# stmotor.net
KiCad netlist of a schematic drawn in EAGLE
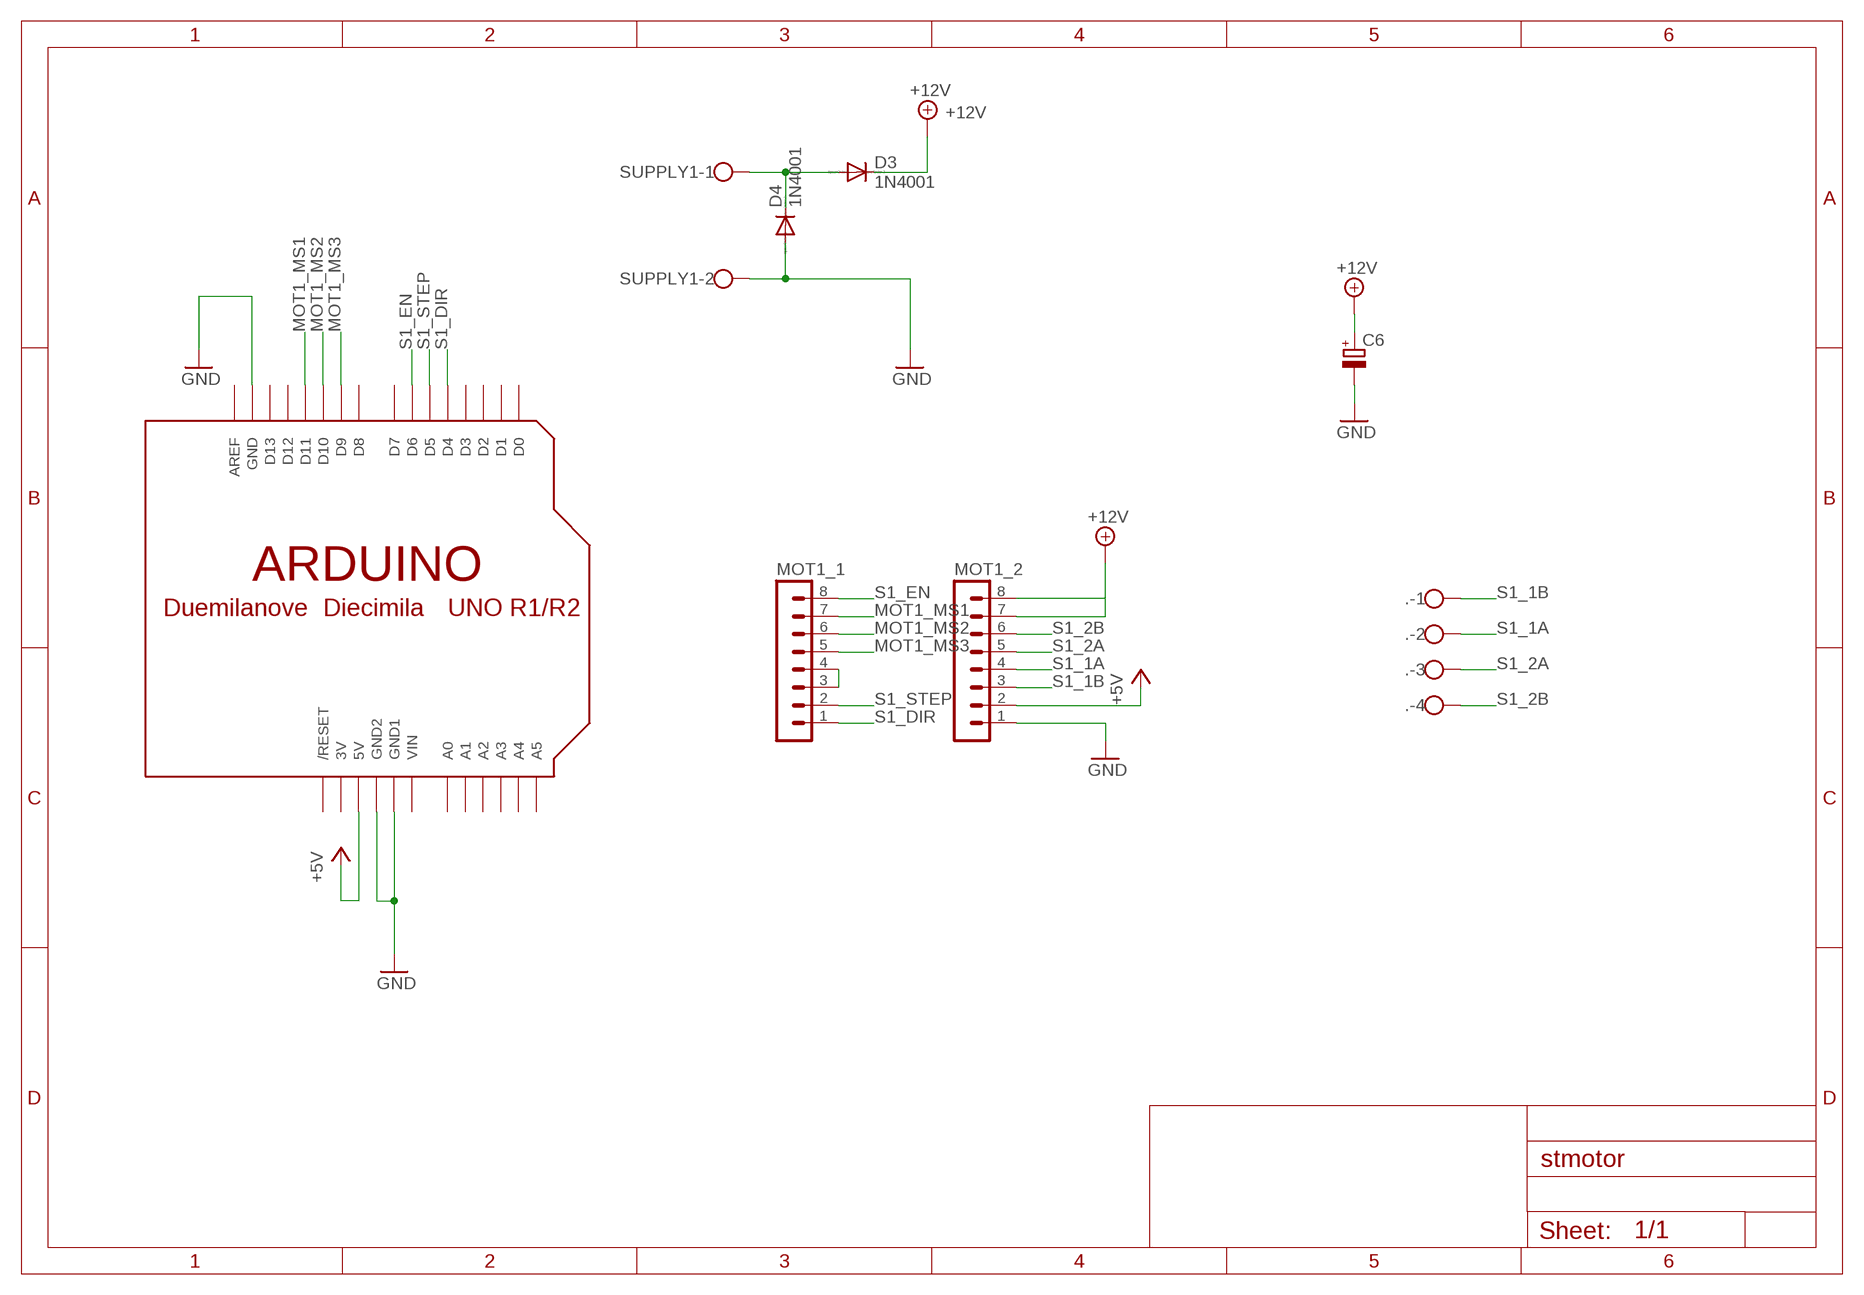
[diagram p0: schematic, sheet 1]

(export (version "E")
  (design (tool "Eeschema 10.0.6"))
  (components
    (comp (ref ".")
      (value "W237-4")
      (footprint "eagle-import:W237-4")
      (libsource (lib "eagle-import") (part "W237-4"))
    )
    (comp (ref "C6")
      (value "CPOL-EU153CLV-0807")
      (footprint "eagle-import:153CLV-0807")
      (libsource (lib "eagle-import") (part "CPOL-EU153CLV-0807"))
    )
    (comp (ref "D3")
      (value "1N4001")
      (footprint "eagle-import:DO41-10")
      (libsource (lib "eagle-import") (part "1N4004"))
    )
    (comp (ref "D4")
      (value "1N4001")
      (footprint "eagle-import:DO41-10")
      (libsource (lib "eagle-import") (part "1N4004"))
    )
    (comp (ref "MOT1_1")
      (value "MA08-1")
      (footprint "eagle-import:MA08-1")
      (libsource (lib "eagle-import") (part "MA08-1"))
    )
    (comp (ref "MOT1_2")
      (value "MA08-1")
      (footprint "eagle-import:MA08-1")
      (libsource (lib "eagle-import") (part "MA08-1"))
    )
    (comp (ref "SUPPLY1")
      (value "W237-102")
      (footprint "eagle-import:W237-102")
      (fields (field (name "MPN") "237-102"))
      (libsource (lib "eagle-import") (part "W237-102"))
    )
    (comp (ref "U$1")
      (value "ARDUINO-NOHOLE")
      (footprint "eagle-import:ARDUINO-NOHOLE")
      (libsource (lib "eagle-import") (part "ARDUINO-NOHOLE"))
    )
  )
  (nets
    (net (code "1") (name "+5V") (class "Default")
      (node (ref "MOT1_2") (pin "2") (pinfunction "2_2") (pintype "passive"))
      (node (ref "U$1") (pin "5V") (pinfunction "5V_5V") (pintype "power_in"))
    )
    (net (code "2") (name "+12V") (class "Default")
      (node (ref "C6") (pin "+") (pinfunction "+_+") (pintype "passive"))
      (node (ref "D3") (pin "C") (pinfunction "C_C") (pintype "passive"))
      (node (ref "MOT1_2") (pin "7") (pinfunction "7_7") (pintype "passive"))
    )
    (net (code "3") (name "/3V") (class "Default")
      (node (ref "U$1") (pin "3V") (pinfunction "3V_3V") (pintype "power_in"))
    )
    (net (code "4") (name "/MOT1_MS1") (class "Default")
      (node (ref "MOT1_1") (pin "7") (pinfunction "7_7") (pintype "passive"))
      (node (ref "U$1") (pin "D11") (pinfunction "D11_D11") (pintype "bidirectional"))
    )
    (net (code "5") (name "/MOT1_MS2") (class "Default")
      (node (ref "MOT1_1") (pin "6") (pinfunction "6_6") (pintype "passive"))
      (node (ref "U$1") (pin "D10") (pinfunction "D10_D10") (pintype "bidirectional"))
    )
    (net (code "6") (name "/MOT1_MS3") (class "Default")
      (node (ref "MOT1_1") (pin "5") (pinfunction "5_5") (pintype "passive"))
      (node (ref "U$1") (pin "D9") (pinfunction "D9_D9") (pintype "bidirectional"))
    )
    (net (code "7") (name "/S1_1A") (class "Default")
      (node (ref ".") (pin "2") (pinfunction "KL_2") (pintype "passive"))
      (node (ref "MOT1_2") (pin "4") (pinfunction "4_4") (pintype "passive"))
    )
    (net (code "8") (name "/S1_1B") (class "Default")
      (node (ref ".") (pin "1") (pinfunction "KL_1") (pintype "passive"))
      (node (ref "MOT1_2") (pin "3") (pinfunction "3_3") (pintype "passive"))
    )
    (net (code "9") (name "/S1_2A") (class "Default")
      (node (ref ".") (pin "3") (pinfunction "KL_3") (pintype "passive"))
      (node (ref "MOT1_2") (pin "5") (pinfunction "5_5") (pintype "passive"))
    )
    (net (code "10") (name "/S1_2B") (class "Default")
      (node (ref ".") (pin "4") (pinfunction "KL_4") (pintype "passive"))
      (node (ref "MOT1_2") (pin "6") (pinfunction "6_6") (pintype "passive"))
    )
    (net (code "11") (name "/S1_DIR") (class "Default")
      (node (ref "MOT1_1") (pin "1") (pinfunction "1_1") (pintype "passive"))
      (node (ref "U$1") (pin "D4") (pinfunction "D4_D4") (pintype "bidirectional"))
    )
    (net (code "12") (name "/S1_EN") (class "Default")
      (node (ref "MOT1_1") (pin "8") (pinfunction "8_8") (pintype "passive"))
      (node (ref "U$1") (pin "D6") (pinfunction "D6_D6") (pintype "bidirectional"))
    )
    (net (code "13") (name "/S1_STEP") (class "Default")
      (node (ref "MOT1_1") (pin "2") (pinfunction "2_2") (pintype "passive"))
      (node (ref "U$1") (pin "D5") (pinfunction "D5_D5") (pintype "bidirectional"))
    )
    (net (code "14") (name "/VIN") (class "Default")
      (node (ref "U$1") (pin "VIN") (pinfunction "VIN_VIN") (pintype "power_in"))
    )
    (net (code "15") (name "GND") (class "Default")
      (node (ref "C6") (pin "-") (pinfunction "-_-") (pintype "passive"))
      (node (ref "D4") (pin "A") (pinfunction "A_A") (pintype "passive"))
      (node (ref "MOT1_2") (pin "1") (pinfunction "1_1") (pintype "passive"))
      (node (ref "SUPPLY1") (pin "2") (pinfunction "KL_2") (pintype "passive"))
      (node (ref "U$1") (pin "GND") (pinfunction "GND_GND") (pintype "power_in"))
      (node (ref "U$1") (pin "GND1") (pinfunction "GND1_GND1") (pintype "power_in"))
      (node (ref "U$1") (pin "GND2") (pinfunction "GND2_GND2") (pintype "power_in"))
    )
    (net (code "16") (name "Net-(MOT1_1-Pad3)") (class "Default")
      (node (ref "MOT1_1") (pin "3") (pinfunction "3_3") (pintype "passive"))
      (node (ref "MOT1_1") (pin "4") (pinfunction "4_4") (pintype "passive"))
    )
    (net (code "17") (name "Net-(SUPPLY1A-KL)") (class "Default")
      (node (ref "D3") (pin "A") (pinfunction "A_A") (pintype "passive"))
      (node (ref "D4") (pin "C") (pinfunction "C_C") (pintype "passive"))
      (node (ref "SUPPLY1") (pin "1") (pinfunction "KL_1") (pintype "passive"))
    )
    (net (code "18") (name "unconnected-(MOT1_2-Pad8)") (class "Default")
      (node (ref "MOT1_2") (pin "8") (pinfunction "8_8") (pintype "passive"))
    )
    (net (code "19") (name "unconnected-(U$1-PadA0)") (class "Default")
      (node (ref "U$1") (pin "A0") (pinfunction "A0_A0") (pintype "bidirectional"))
    )
    (net (code "20") (name "unconnected-(U$1-PadA1)") (class "Default")
      (node (ref "U$1") (pin "A1") (pinfunction "A1_A1") (pintype "bidirectional"))
    )
    (net (code "21") (name "unconnected-(U$1-PadA2)") (class "Default")
      (node (ref "U$1") (pin "A2") (pinfunction "A2_A2") (pintype "bidirectional"))
    )
    (net (code "22") (name "unconnected-(U$1-PadA3)") (class "Default")
      (node (ref "U$1") (pin "A3") (pinfunction "A3_A3") (pintype "bidirectional"))
    )
    (net (code "23") (name "unconnected-(U$1-PadA4)") (class "Default")
      (node (ref "U$1") (pin "A4") (pinfunction "A4_A4") (pintype "bidirectional"))
    )
    (net (code "24") (name "unconnected-(U$1-PadA5)") (class "Default")
      (node (ref "U$1") (pin "A5") (pinfunction "A5_A5") (pintype "bidirectional"))
    )
    (net (code "25") (name "unconnected-(U$1-PadAREF)") (class "Default")
      (node (ref "U$1") (pin "AREF") (pinfunction "AREF_AREF") (pintype "bidirectional"))
    )
    (net (code "26") (name "unconnected-(U$1-PadD0)") (class "Default")
      (node (ref "U$1") (pin "D0") (pinfunction "D0_D0") (pintype "bidirectional"))
    )
    (net (code "27") (name "unconnected-(U$1-PadD1)") (class "Default")
      (node (ref "U$1") (pin "D1") (pinfunction "D1_D1") (pintype "bidirectional"))
    )
    (net (code "28") (name "unconnected-(U$1-PadD2)") (class "Default")
      (node (ref "U$1") (pin "D2") (pinfunction "D2_D2") (pintype "bidirectional"))
    )
    (net (code "29") (name "unconnected-(U$1-PadD3)") (class "Default")
      (node (ref "U$1") (pin "D3") (pinfunction "D3_D3") (pintype "bidirectional"))
    )
    (net (code "30") (name "unconnected-(U$1-PadD7)") (class "Default")
      (node (ref "U$1") (pin "D7") (pinfunction "D7_D7") (pintype "bidirectional"))
    )
    (net (code "31") (name "unconnected-(U$1-PadD8)") (class "Default")
      (node (ref "U$1") (pin "D8") (pinfunction "D8_D8") (pintype "bidirectional"))
    )
    (net (code "32") (name "unconnected-(U$1-PadD12)") (class "Default")
      (node (ref "U$1") (pin "D12") (pinfunction "D12_D12") (pintype "bidirectional"))
    )
    (net (code "33") (name "unconnected-(U$1-PadD13)") (class "Default")
      (node (ref "U$1") (pin "D13") (pinfunction "D13_D13") (pintype "bidirectional"))
    )
    (net (code "34") (name "unconnected-(U$1-{slash}RESET-PadRESET)") (class "Default")
      (node (ref "U$1") (pin "RESET") (pinfunction "/RESET_RESET") (pintype "bidirectional"))
    )
  )
)
